# radio_am_4bjt.net
KiCad netlist of a schematic drawn in EAGLE
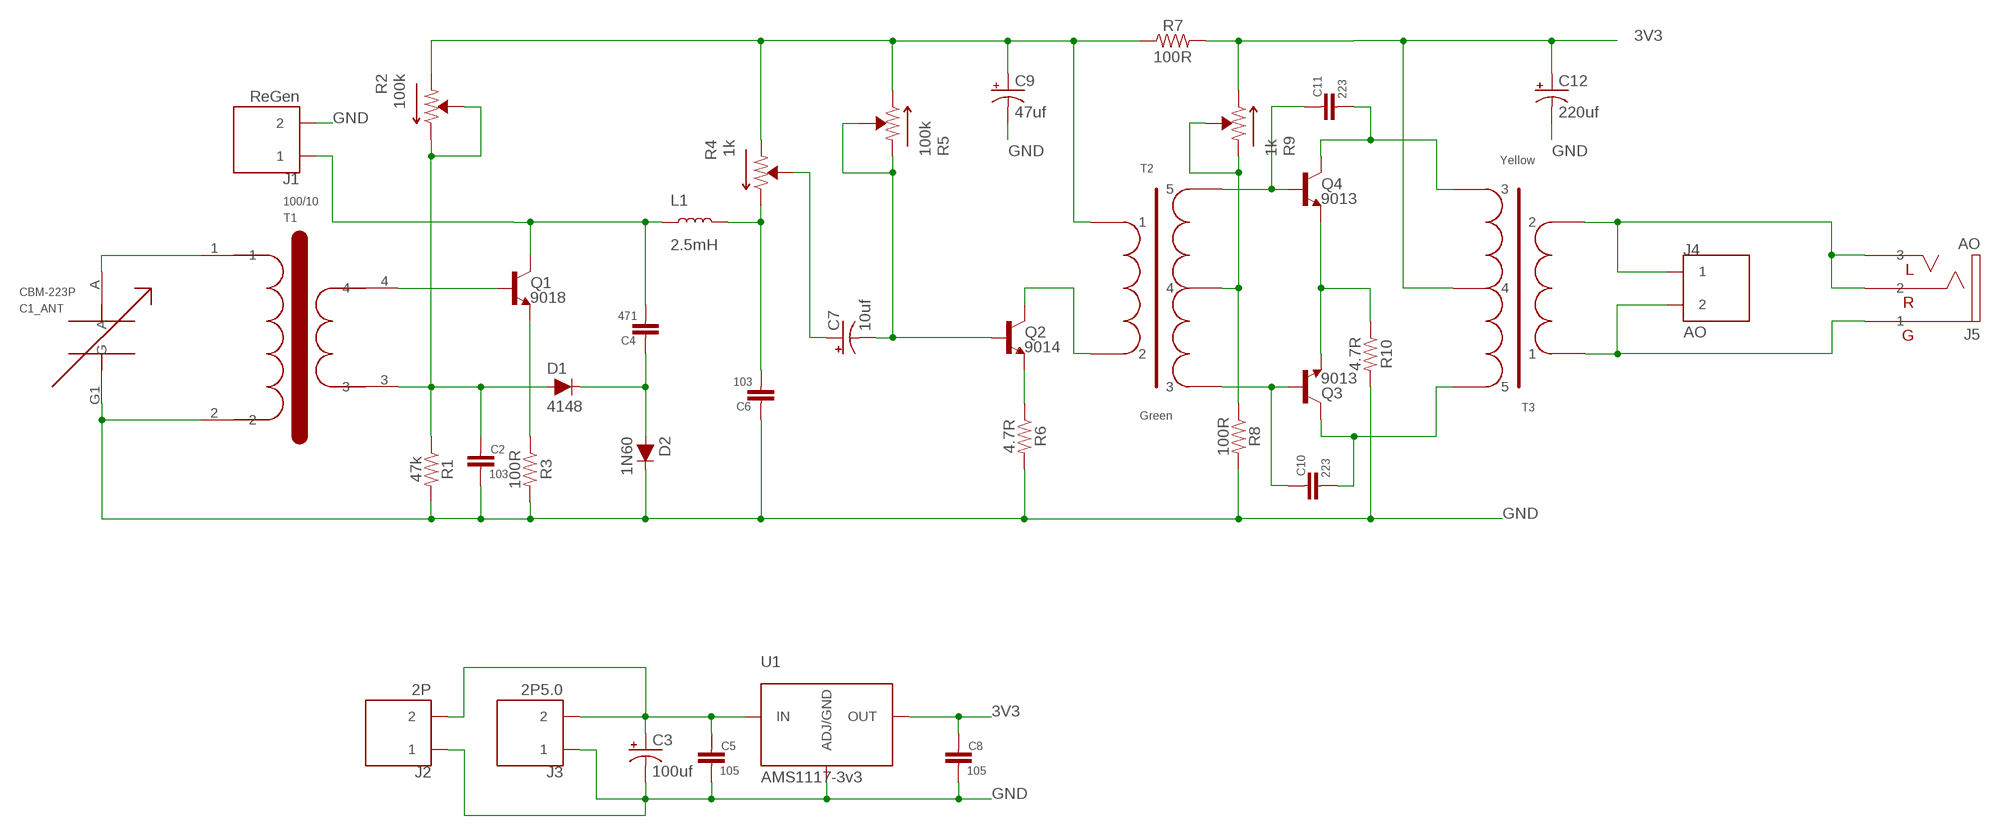
[diagram p0: schematic, sheet 1]

(export (version "E")
  (design (tool "Eeschema 10.0.6"))
  (components
    (comp (ref "C1")
      (value "CBM-223P")
      (footprint "eagle-import:CBM-223P")
      (libsource (lib "eagle-import") (part "CBM-223P"))
    )
    (comp (ref "C2")
      (value "103")
      (footprint "eagle-import:CAP_5MM")
      (libsource (lib "eagle-import") (part "CAP_P"))
    )
    (comp (ref "C3")
      (value "100uf")
      (footprint "eagle-import:CAP_2.5MM")
      (libsource (lib "eagle-import") (part "CAP"))
    )
    (comp (ref "C4")
      (value "471")
      (footprint "eagle-import:CAP_5MM")
      (libsource (lib "eagle-import") (part "CAP_P"))
    )
    (comp (ref "C5")
      (value "105")
      (footprint "eagle-import:CAP_5MM")
      (libsource (lib "eagle-import") (part "CAP_P"))
    )
    (comp (ref "C6")
      (value "103")
      (footprint "eagle-import:CAP_5MM")
      (libsource (lib "eagle-import") (part "CAP_P"))
    )
    (comp (ref "C7")
      (value "10uf")
      (footprint "eagle-import:CAP_2MM")
      (libsource (lib "eagle-import") (part "CAP2MM"))
    )
    (comp (ref "C8")
      (value "105")
      (footprint "eagle-import:CAP_5MM")
      (libsource (lib "eagle-import") (part "CAP_P"))
    )
    (comp (ref "C9")
      (value "47uf")
      (footprint "eagle-import:CAP_2MM")
      (libsource (lib "eagle-import") (part "CAP2MM"))
    )
    (comp (ref "C10")
      (value "223")
      (footprint "eagle-import:CAP_5MM")
      (libsource (lib "eagle-import") (part "CAP_P"))
    )
    (comp (ref "C11")
      (value "223")
      (footprint "eagle-import:CAP_5MM")
      (libsource (lib "eagle-import") (part "CAP_P"))
    )
    (comp (ref "C12")
      (value "220uf")
      (footprint "eagle-import:CAP_2.5MM")
      (libsource (lib "eagle-import") (part "CAP"))
    )
    (comp (ref "D1")
      (value "4148")
      (footprint "eagle-import:DIODE-1N4148")
      (libsource (lib "eagle-import") (part "DIODE-1N4148"))
    )
    (comp (ref "D2")
      (value "1N60")
      (footprint "eagle-import:DIODE-1N4148")
      (libsource (lib "eagle-import") (part "DIODE-1N4148"))
    )
    (comp (ref "J1")
      (value "ReGen")
      (footprint "eagle-import:2P_2.54MM")
      (libsource (lib "eagle-import") (part "2P"))
    )
    (comp (ref "J2")
      (value "2P")
      (footprint "eagle-import:2P_2.54MM")
      (libsource (lib "eagle-import") (part "2P"))
    )
    (comp (ref "J3")
      (value "2P5.0")
      (footprint "eagle-import:2P_5.08MM")
      (libsource (lib "eagle-import") (part "2P5.0"))
    )
    (comp (ref "J4")
      (value "AO")
      (footprint "eagle-import:2P_5.08MM")
      (libsource (lib "eagle-import") (part "2P5.0"))
    )
    (comp (ref "J5")
      (value "AO")
      (footprint "eagle-import:3.5MM")
      (libsource (lib "eagle-import") (part "3.5MM_PHONE"))
    )
    (comp (ref "L1")
      (value "2.5mH")
      (footprint "eagle-import:VLU0810")
      (libsource (lib "eagle-import") (part "INDUCTOR_PTH"))
    )
    (comp (ref "Q1")
      (value "9018")
      (footprint "eagle-import:TO-92")
      (libsource (lib "eagle-import") (part "TRANS_NPN-2N3904"))
    )
    (comp (ref "Q2")
      (value "9014")
      (footprint "eagle-import:TO-92")
      (libsource (lib "eagle-import") (part "TRANS_NPN-2N3904"))
    )
    (comp (ref "Q3")
      (value "9013")
      (footprint "eagle-import:TO-92")
      (libsource (lib "eagle-import") (part "TRANS_NPN-2N3904"))
    )
    (comp (ref "Q4")
      (value "9013")
      (footprint "eagle-import:TO-92")
      (libsource (lib "eagle-import") (part "TRANS_NPN-2N3904"))
    )
    (comp (ref "R1")
      (value "47k")
      (footprint "eagle-import:AXIAL-0.3")
      (libsource (lib "eagle-import") (part "RESISTORAXIAL-0.3"))
    )
    (comp (ref "R2")
      (value "100k")
      (footprint "eagle-import:3362P")
      (libsource (lib "eagle-import") (part "RES_ADJ"))
    )
    (comp (ref "R3")
      (value "100R")
      (footprint "eagle-import:AXIAL-0.3")
      (libsource (lib "eagle-import") (part "RESISTORAXIAL-0.3"))
    )
    (comp (ref "R4")
      (value "1k")
      (footprint "eagle-import:3362P")
      (libsource (lib "eagle-import") (part "RES_ADJ"))
    )
    (comp (ref "R5")
      (value "100k")
      (footprint "eagle-import:3362P")
      (libsource (lib "eagle-import") (part "RES_ADJ"))
    )
    (comp (ref "R6")
      (value "4.7R")
      (footprint "eagle-import:AXIAL-0.3")
      (libsource (lib "eagle-import") (part "RESISTORAXIAL-0.3"))
    )
    (comp (ref "R7")
      (value "100R")
      (footprint "eagle-import:AXIAL-0.3")
      (libsource (lib "eagle-import") (part "RESISTORAXIAL-0.3"))
    )
    (comp (ref "R8")
      (value "100R")
      (footprint "eagle-import:AXIAL-0.3")
      (libsource (lib "eagle-import") (part "RESISTORAXIAL-0.3"))
    )
    (comp (ref "R9")
      (value "1k")
      (footprint "eagle-import:3362P")
      (libsource (lib "eagle-import") (part "RES_ADJ"))
    )
    (comp (ref "R10")
      (value "4.7R")
      (footprint "eagle-import:AXIAL-0.3")
      (libsource (lib "eagle-import") (part "RESISTORAXIAL-0.3"))
    )
    (comp (ref "T1")
      (value "100/10")
      (footprint "eagle-import:AM_ANT_COIL")
      (libsource (lib "eagle-import") (part "AM_ANT_COIL"))
    )
    (comp (ref "T2")
      (value "Green")
      (footprint "eagle-import:TRANSFORMER_BJT_PP_2_4")
      (libsource (lib "eagle-import") (part "TRANSFORMER_BJT_PP"))
    )
    (comp (ref "T3")
      (value "Yellow")
      (footprint "eagle-import:TRANSFORMER_BJT_PP_2_4")
      (libsource (lib "eagle-import") (part "TRANSFORMER_BJT_PP"))
    )
    (comp (ref "U1")
      (value "AMS1117-3v3")
      (footprint "eagle-import:SOT-223")
      (libsource (lib "eagle-import") (part "AMS1117"))
    )
  )
  (nets
    (net (code "1") (name "/3V3") (class "Default")
      (node (ref "C12") (pin "+") (pinfunction "+_+") (pintype "passive"))
      (node (ref "C8") (pin "P$1") (pinfunction "1_P$1") (pintype "passive"))
      (node (ref "R7") (pin "P$2") (pinfunction "2_P$2") (pintype "passive"))
      (node (ref "R9") (pin "P$3") (pinfunction "3_P$3") (pintype "passive"))
      (node (ref "T3") (pin "4") (pinfunction "4_4") (pintype "bidirectional"))
      (node (ref "U1") (pin "2") (pinfunction "OUT_2") (pintype "bidirectional"))
      (node (ref "U1") (pin "4") (pinfunction "OUT_4") (pintype "bidirectional"))
    )
    (net (code "2") (name "/GND") (class "Default")
      (node (ref "C1") (pin "G1") (pinfunction "G_G1") (pintype "bidirectional"))
      (node (ref "C12") (pin "-") (pinfunction "-_-") (pintype "passive"))
      (node (ref "C2") (pin "P$2") (pinfunction "2_P$2") (pintype "passive"))
      (node (ref "C3") (pin "-") (pinfunction "-_-") (pintype "passive"))
      (node (ref "C5") (pin "P$2") (pinfunction "2_P$2") (pintype "passive"))
      (node (ref "C6") (pin "P$1") (pinfunction "1_P$1") (pintype "passive"))
      (node (ref "C8") (pin "P$2") (pinfunction "2_P$2") (pintype "passive"))
      (node (ref "C9") (pin "-") (pinfunction "-_-") (pintype "passive"))
      (node (ref "D2") (pin "C") (pinfunction "C_C") (pintype "passive"))
      (node (ref "J1") (pin "2") (pinfunction "2_2") (pintype "bidirectional"))
      (node (ref "J2") (pin "1") (pinfunction "1_1") (pintype "bidirectional"))
      (node (ref "J3") (pin "L") (pinfunction "1_L") (pintype "bidirectional"))
      (node (ref "R1") (pin "P$2") (pinfunction "2_P$2") (pintype "passive"))
      (node (ref "R10") (pin "P$2") (pinfunction "2_P$2") (pintype "passive"))
      (node (ref "R3") (pin "P$2") (pinfunction "2_P$2") (pintype "passive"))
      (node (ref "R6") (pin "P$2") (pinfunction "2_P$2") (pintype "passive"))
      (node (ref "R8") (pin "P$2") (pinfunction "2_P$2") (pintype "passive"))
      (node (ref "T1") (pin "2") (pinfunction "2_2") (pintype "bidirectional"))
      (node (ref "U1") (pin "1") (pinfunction "ADJ/GND_1") (pintype "bidirectional"))
    )
    (net (code "3") (name "Net-(C1-PadA)") (class "Default")
      (node (ref "C1") (pin "A") (pinfunction "A_A") (pintype "bidirectional"))
      (node (ref "T1") (pin "1") (pinfunction "1_1") (pintype "bidirectional"))
    )
    (net (code "4") (name "Net-(C2-1)") (class "Default")
      (node (ref "C2") (pin "P$1") (pinfunction "1_P$1") (pintype "passive"))
      (node (ref "D1") (pin "A") (pinfunction "A_A") (pintype "passive"))
      (node (ref "R1") (pin "P$1") (pinfunction "1_P$1") (pintype "passive"))
      (node (ref "R2") (pin "P$2") (pinfunction "2_P$2") (pintype "passive"))
      (node (ref "R2") (pin "P$3") (pinfunction "3_P$3") (pintype "passive"))
      (node (ref "T1") (pin "3") (pinfunction "3_3") (pintype "bidirectional"))
    )
    (net (code "5") (name "Net-(C4-1)") (class "Default")
      (node (ref "C4") (pin "P$1") (pinfunction "1_P$1") (pintype "passive"))
      (node (ref "D1") (pin "C") (pinfunction "C_C") (pintype "passive"))
      (node (ref "D2") (pin "A") (pinfunction "A_A") (pintype "passive"))
    )
    (net (code "6") (name "Net-(C4-2)") (class "Default")
      (node (ref "C4") (pin "P$2") (pinfunction "2_P$2") (pintype "passive"))
      (node (ref "J1") (pin "1") (pinfunction "1_1") (pintype "bidirectional"))
      (node (ref "L1") (pin "+") (pinfunction "1_+") (pintype "passive"))
      (node (ref "Q1") (pin "3") (pinfunction "C_3") (pintype "passive"))
    )
    (net (code "7") (name "Net-(C5-1)") (class "Default")
      (node (ref "C3") (pin "+") (pinfunction "+_+") (pintype "passive"))
      (node (ref "C5") (pin "P$1") (pinfunction "1_P$1") (pintype "passive"))
      (node (ref "J2") (pin "2") (pinfunction "2_2") (pintype "bidirectional"))
      (node (ref "J3") (pin "N") (pinfunction "2_N") (pintype "bidirectional"))
      (node (ref "U1") (pin "3") (pinfunction "IN_3") (pintype "bidirectional"))
    )
    (net (code "8") (name "Net-(C6-2)") (class "Default")
      (node (ref "C6") (pin "P$2") (pinfunction "2_P$2") (pintype "passive"))
      (node (ref "L1") (pin "-") (pinfunction "2_-") (pintype "passive"))
      (node (ref "R4") (pin "P$3") (pinfunction "3_P$3") (pintype "passive"))
    )
    (net (code "9") (name "Net-(C10-1)") (class "Default")
      (node (ref "C10") (pin "P$1") (pinfunction "1_P$1") (pintype "passive"))
      (node (ref "Q3") (pin "2") (pinfunction "B_2") (pintype "passive"))
      (node (ref "T2") (pin "3") (pinfunction "3_3") (pintype "bidirectional"))
    )
    (net (code "10") (name "Net-(C10-2)") (class "Default")
      (node (ref "C10") (pin "P$2") (pinfunction "2_P$2") (pintype "passive"))
      (node (ref "Q3") (pin "3") (pinfunction "C_3") (pintype "passive"))
      (node (ref "T3") (pin "5") (pinfunction "5_5") (pintype "bidirectional"))
    )
    (net (code "11") (name "Net-(C11-1)") (class "Default")
      (node (ref "C11") (pin "P$1") (pinfunction "1_P$1") (pintype "passive"))
      (node (ref "Q4") (pin "2") (pinfunction "B_2") (pintype "passive"))
      (node (ref "T2") (pin "5") (pinfunction "5_5") (pintype "bidirectional"))
    )
    (net (code "12") (name "Net-(C11-2)") (class "Default")
      (node (ref "C11") (pin "P$2") (pinfunction "2_P$2") (pintype "passive"))
      (node (ref "Q4") (pin "3") (pinfunction "C_3") (pintype "passive"))
      (node (ref "T3") (pin "3") (pinfunction "3_3") (pintype "bidirectional"))
    )
    (net (code "13") (name "Net-(J4-1)") (class "Default")
      (node (ref "J4") (pin "L") (pinfunction "1_L") (pintype "bidirectional"))
      (node (ref "J5") (pin "P$2") (pinfunction "2_P$2") (pintype "bidirectional"))
      (node (ref "J5") (pin "P$3") (pinfunction "3_P$3") (pintype "bidirectional"))
      (node (ref "T3") (pin "2") (pinfunction "2_2") (pintype "bidirectional"))
    )
    (net (code "14") (name "Net-(J4-2)") (class "Default")
      (node (ref "J4") (pin "N") (pinfunction "2_N") (pintype "bidirectional"))
      (node (ref "J5") (pin "P$1") (pinfunction "1_P$1") (pintype "bidirectional"))
      (node (ref "T3") (pin "1") (pinfunction "1_1") (pintype "bidirectional"))
    )
    (net (code "15") (name "Net-(Q1-B)") (class "Default")
      (node (ref "Q1") (pin "2") (pinfunction "B_2") (pintype "passive"))
      (node (ref "T1") (pin "4") (pinfunction "4_4") (pintype "bidirectional"))
    )
    (net (code "16") (name "Net-(Q1-E)") (class "Default")
      (node (ref "Q1") (pin "1") (pinfunction "E_1") (pintype "passive"))
      (node (ref "R3") (pin "P$1") (pinfunction "1_P$1") (pintype "passive"))
    )
    (net (code "17") (name "Net-(Q2-B)") (class "Default")
      (node (ref "C7") (pin "-") (pinfunction "-_-") (pintype "passive"))
      (node (ref "Q2") (pin "2") (pinfunction "B_2") (pintype "passive"))
      (node (ref "R5") (pin "P$1") (pinfunction "1_P$1") (pintype "passive"))
      (node (ref "R5") (pin "P$2") (pinfunction "2_P$2") (pintype "passive"))
    )
    (net (code "18") (name "Net-(Q2-C)") (class "Default")
      (node (ref "Q2") (pin "3") (pinfunction "C_3") (pintype "passive"))
      (node (ref "T2") (pin "2") (pinfunction "2_2") (pintype "bidirectional"))
    )
    (net (code "19") (name "Net-(Q2-E)") (class "Default")
      (node (ref "Q2") (pin "1") (pinfunction "E_1") (pintype "passive"))
      (node (ref "R6") (pin "P$1") (pinfunction "1_P$1") (pintype "passive"))
    )
    (net (code "20") (name "Net-(Q3-E)") (class "Default")
      (node (ref "Q3") (pin "1") (pinfunction "E_1") (pintype "passive"))
      (node (ref "Q4") (pin "1") (pinfunction "E_1") (pintype "passive"))
      (node (ref "R10") (pin "P$1") (pinfunction "1_P$1") (pintype "passive"))
    )
    (net (code "21") (name "Net-(R2-1)") (class "Default")
      (node (ref "C9") (pin "+") (pinfunction "+_+") (pintype "passive"))
      (node (ref "R2") (pin "P$1") (pinfunction "1_P$1") (pintype "passive"))
      (node (ref "R4") (pin "P$1") (pinfunction "1_P$1") (pintype "passive"))
      (node (ref "R5") (pin "P$3") (pinfunction "3_P$3") (pintype "passive"))
      (node (ref "R7") (pin "P$1") (pinfunction "1_P$1") (pintype "passive"))
      (node (ref "T2") (pin "1") (pinfunction "1_1") (pintype "bidirectional"))
    )
    (net (code "22") (name "Net-(R4-2)") (class "Default")
      (node (ref "C7") (pin "+") (pinfunction "+_+") (pintype "passive"))
      (node (ref "R4") (pin "P$2") (pinfunction "2_P$2") (pintype "passive"))
    )
    (net (code "23") (name "Net-(R8-1)") (class "Default")
      (node (ref "R8") (pin "P$1") (pinfunction "1_P$1") (pintype "passive"))
      (node (ref "R9") (pin "P$1") (pinfunction "1_P$1") (pintype "passive"))
      (node (ref "R9") (pin "P$2") (pinfunction "2_P$2") (pintype "passive"))
      (node (ref "T2") (pin "4") (pinfunction "4_4") (pintype "bidirectional"))
    )
  )
)
